# top.net
KiCad netlist of a schematic drawn in Altium Designer
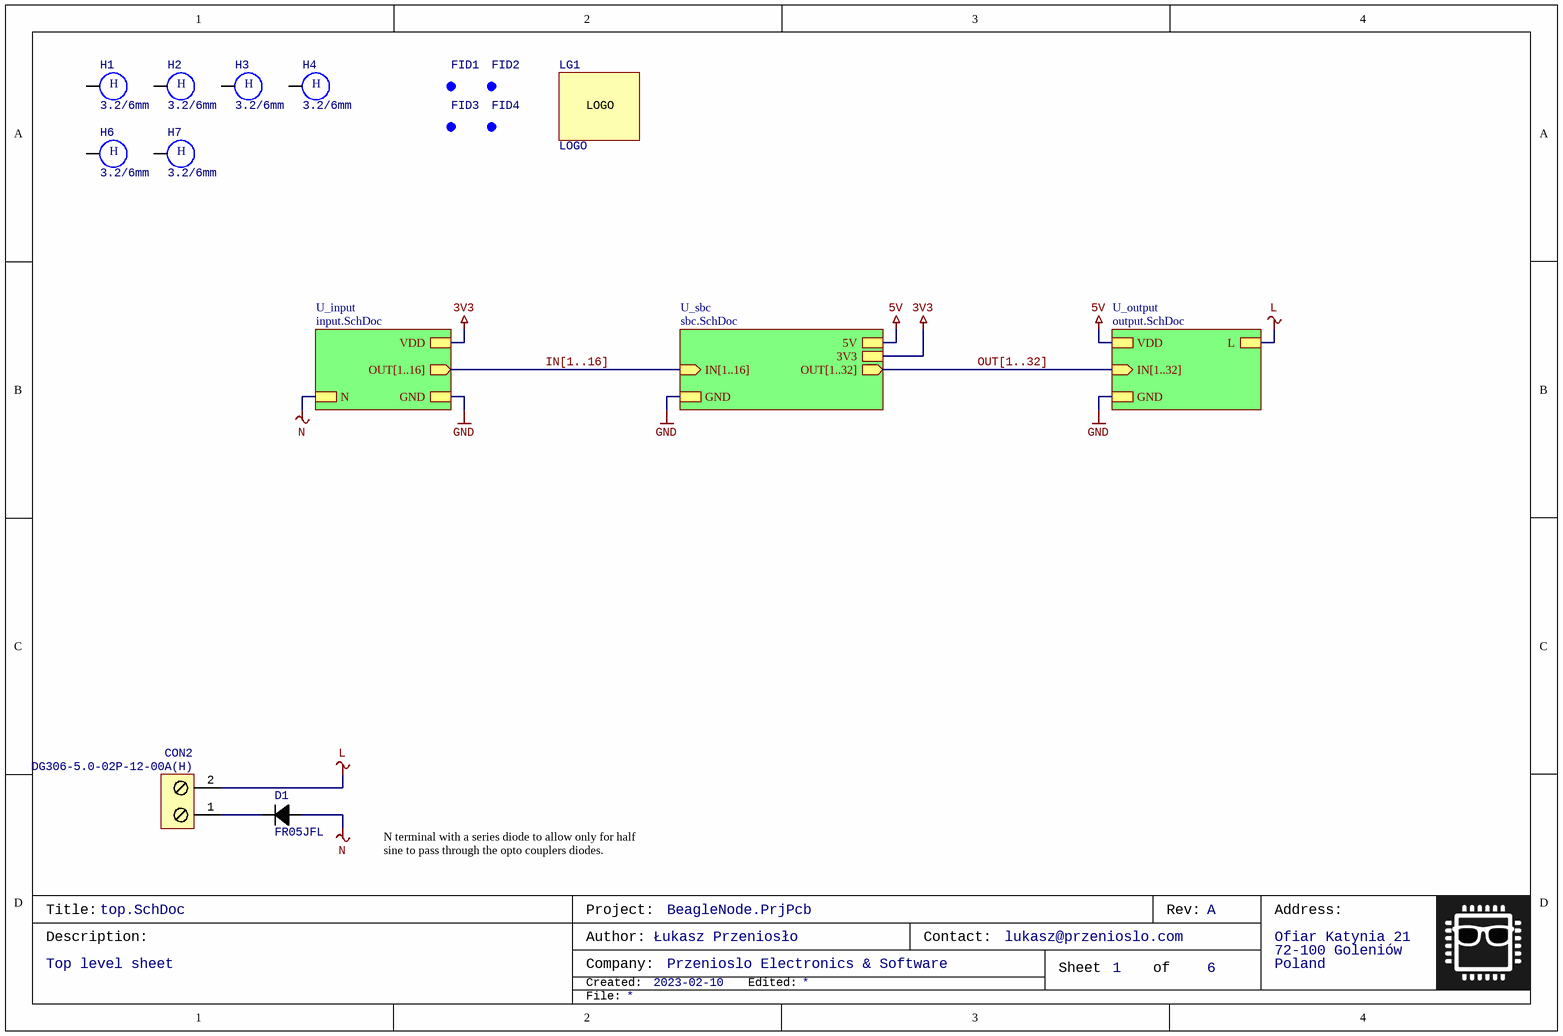
[diagram p0: top.SchDoc]

(export (version "E")
  (design (tool "Eeschema 10.0.6"))
  (components
    (comp (ref "CON2")
      (value "DG306-5.0-02P-12-00A(H)")
      (footprint "Terminal-block-2way-5.0")
      (description "Screwed terminal block with 2 pins")
      (fields (field (name "MANUFACTURER") "DEGSON ELECTRONICS"))
      (libsource (lib "connector") (part "Terminal Block 2"))
    )
    (comp (ref "D1")
      (value "FR05JFL")
      (footprint "SOD323")
      (description "FAST RECOVERY SURFACE MOUNT GLASS PASSIVATED RECTIFIER")
      (fields (field (name "MANUFACTURER") "DC Components"))
      (libsource (lib "diode") (part "FR05xFL"))
    )
    (comp (ref "FID1")
      (value "Generic fidutial")
      (footprint "FID_ROUND")
      (description "Optical alignement fidutial PCB element (not visible in bom)")
      (libsource (lib "nonelectrical") (part "FID"))
    )
    (comp (ref "FID2")
      (value "Generic fidutial")
      (footprint "FID_ROUND")
      (description "Optical alignement fidutial PCB element (not visible in bom)")
      (libsource (lib "nonelectrical") (part "FID"))
    )
    (comp (ref "FID3")
      (value "Generic fidutial")
      (footprint "FID_ROUND")
      (description "Optical alignement fidutial PCB element (not visible in bom)")
      (libsource (lib "nonelectrical") (part "FID"))
    )
    (comp (ref "FID4")
      (value "Generic fidutial")
      (footprint "FID_ROUND")
      (description "Optical alignement fidutial PCB element (not visible in bom)")
      (libsource (lib "nonelectrical") (part "FID"))
    )
    (comp (ref "H1")
      (value "3.2/6mm")
      (footprint "hole-3.2/6")
      (description "Generic hole component with 1 electrical connection")
      (libsource (lib "hole") (part "hole_metalized"))
    )
    (comp (ref "H2")
      (value "3.2/6mm")
      (footprint "hole-3.2/6")
      (description "Generic hole component with 1 electrical connection")
      (libsource (lib "hole") (part "hole_metalized"))
    )
    (comp (ref "H3")
      (value "3.2/6mm")
      (footprint "hole-3.2/6")
      (description "Generic hole component with 1 electrical connection")
      (libsource (lib "hole") (part "hole_metalized"))
    )
    (comp (ref "H4")
      (value "3.2/6mm")
      (footprint "hole-3.2/6")
      (description "Generic hole component with 1 electrical connection")
      (libsource (lib "hole") (part "hole_metalized"))
    )
    (comp (ref "H6")
      (value "3.2/6mm")
      (footprint "hole-3.2/6")
      (description "Generic hole component with 1 electrical connection")
      (libsource (lib "hole") (part "hole_metalized"))
    )
    (comp (ref "H7")
      (value "3.2/6mm")
      (footprint "hole-3.2/6")
      (description "Generic hole component with 1 electrical connection")
      (libsource (lib "hole") (part "hole_metalized"))
    )
    (comp (ref "LG1")
      (value "LOGO")
      (footprint "LOGO_ENS")
      (description "Logo graphical object")
      (libsource (lib "nonelectrical") (part "LOGO"))
    )
  )
  (nets
    (net (code "54") (name "L") (class "Default")
      (node (ref "CON2") (pin "2") (pinfunction "2_2") (pintype "passive"))
    )
    (net (code "55") (name "N") (class "Default")
      (node (ref "D1") (pin "2") (pinfunction "A_2") (pintype "passive"))
    )
    (net (code "56") (name "Net-(D1-K)") (class "Default")
      (node (ref "CON2") (pin "1") (pinfunction "1_1") (pintype "passive"))
      (node (ref "D1") (pin "1") (pinfunction "K_1") (pintype "passive"))
    )
    (net (code "57") (name "unconnected-(H1-Pad1)") (class "Default")
      (node (ref "H1") (pin "1") (pinfunction "1_1") (pintype "passive"))
    )
    (net (code "58") (name "unconnected-(H2-Pad1)") (class "Default")
      (node (ref "H2") (pin "1") (pinfunction "1_1") (pintype "passive"))
    )
    (net (code "59") (name "unconnected-(H3-Pad1)") (class "Default")
      (node (ref "H3") (pin "1") (pinfunction "1_1") (pintype "passive"))
    )
    (net (code "60") (name "unconnected-(H4-Pad1)") (class "Default")
      (node (ref "H4") (pin "1") (pinfunction "1_1") (pintype "passive"))
    )
    (net (code "61") (name "unconnected-(H6-Pad1)") (class "Default")
      (node (ref "H6") (pin "1") (pinfunction "1_1") (pintype "passive"))
    )
    (net (code "62") (name "unconnected-(H7-Pad1)") (class "Default")
      (node (ref "H7") (pin "1") (pinfunction "1_1") (pintype "passive"))
    )
  )
)
